# fuse-b-2.net
KiCad netlist of a schematic drawn in EAGLE
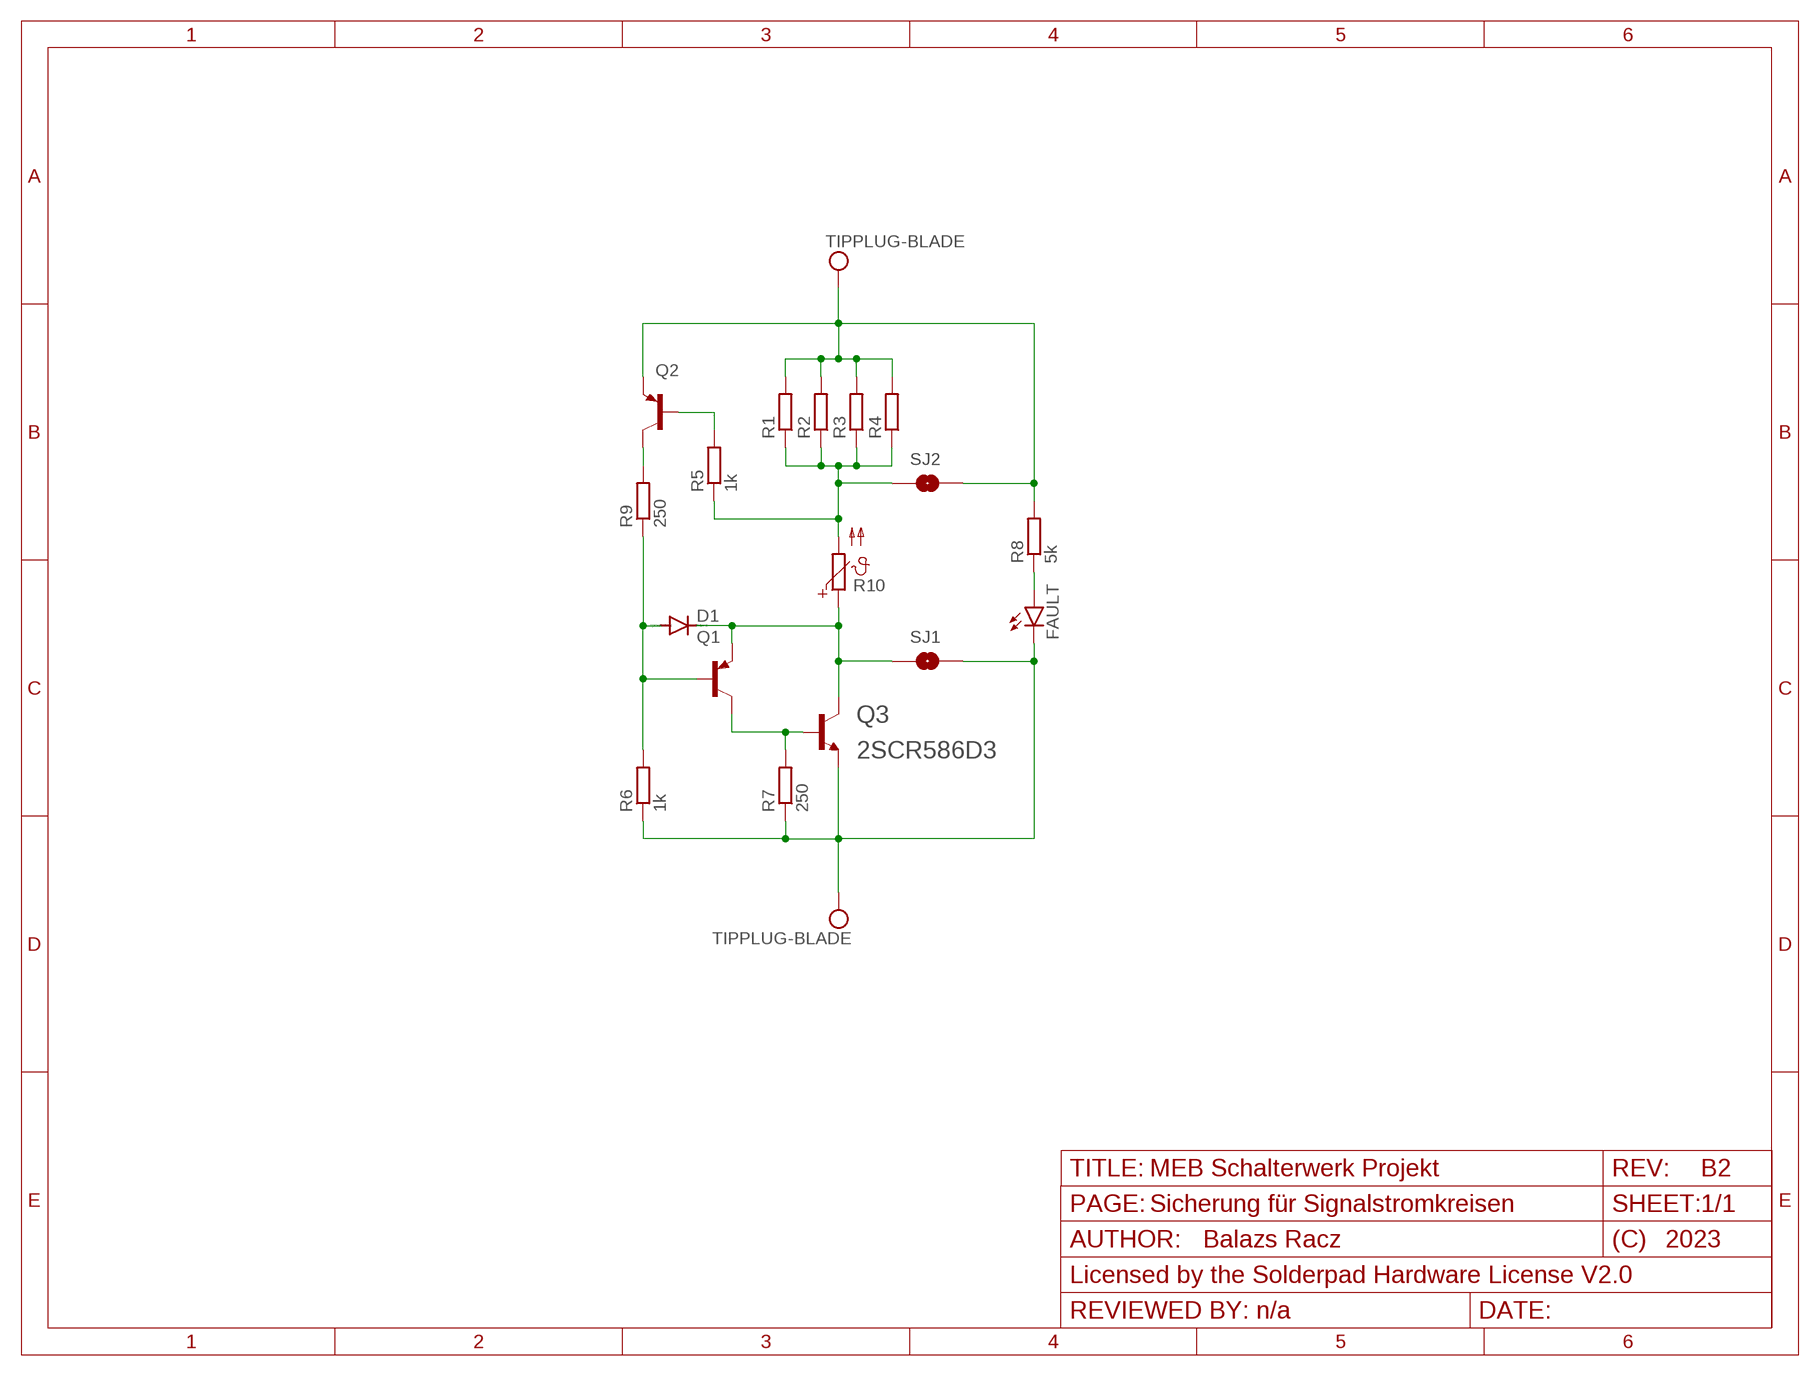
[diagram p0: schematic, sheet 1]

(export (version "E")
  (design (tool "Eeschema 10.0.6"))
  (components
    (comp (ref "D1")
      (value "DIODE-MINIMELF")
      (footprint "eagle-import:MINIMELF")
      (libsource (lib "eagle-import") (part "DIODE-MINIMELF"))
    )
    (comp (ref "FAULT")
      (value "LEDCHIPLED_0603")
      (footprint "eagle-import:CHIPLED_0603")
      (libsource (lib "eagle-import") (part "LEDCHIPLED_0603"))
    )
    (comp (ref "Q1")
      (value "BCX71SMD")
      (footprint "eagle-import:SOT23")
      (libsource (lib "eagle-import") (part "BCX71SMD"))
    )
    (comp (ref "Q2")
      (value "BCX71SMD")
      (footprint "eagle-import:SOT23")
      (libsource (lib "eagle-import") (part "BCX71SMD"))
    )
    (comp (ref "Q3")
      (value "2SCR586D3")
      (footprint "eagle-import:D-PAK_TO252AA")
      (libsource (lib "eagle-import") (part "2SCR586D3TL1"))
    )
    (comp (ref "R1")
      (value "R-EU_R2512")
      (footprint "eagle-import:R2512")
      (libsource (lib "eagle-import") (part "R-EU_R2512"))
    )
    (comp (ref "R2")
      (value "R-EU_R2512")
      (footprint "eagle-import:R2512")
      (libsource (lib "eagle-import") (part "R-EU_R2512"))
    )
    (comp (ref "R3")
      (value "R-EU_R2512")
      (footprint "eagle-import:R2512")
      (libsource (lib "eagle-import") (part "R-EU_R2512"))
    )
    (comp (ref "R4")
      (value "R-EU_R2512")
      (footprint "eagle-import:R2512")
      (libsource (lib "eagle-import") (part "R-EU_R2512"))
    )
    (comp (ref "R5")
      (value "1k")
      (footprint "eagle-import:R0805")
      (libsource (lib "eagle-import") (part "R-EU_R0805"))
    )
    (comp (ref "R6")
      (value "1k")
      (footprint "eagle-import:R0805")
      (libsource (lib "eagle-import") (part "R-EU_R0805"))
    )
    (comp (ref "R7")
      (value "250")
      (footprint "eagle-import:R0805")
      (libsource (lib "eagle-import") (part "R-EU_R0805"))
    )
    (comp (ref "R8")
      (value "5k")
      (footprint "eagle-import:R0805")
      (libsource (lib "eagle-import") (part "R-EU_R0805"))
    )
    (comp (ref "R9")
      (value "250")
      (footprint "eagle-import:R0805")
      (libsource (lib "eagle-import") (part "R-EU_R0805"))
    )
    (comp (ref "R10")
      (value "PTC_1812")
      (footprint "eagle-import:PTC1812")
      (libsource (lib "eagle-import") (part "PTC_1812"))
    )
    (comp (ref "SJ1")
      (value "SJRND2")
      (footprint "eagle-import:SJ_RND2")
      (libsource (lib "eagle-import") (part "SJRND2"))
    )
    (comp (ref "SJ2")
      (value "SJRND2")
      (footprint "eagle-import:SJ_RND2")
      (libsource (lib "eagle-import") (part "SJRND2"))
    )
    (comp (ref "U$1")
      (value "TIPPLUG-BLADE")
      (footprint "eagle-import:BLADEPLUG-9.5X1.25")
      (libsource (lib "eagle-import") (part "TIPPLUG-BLADE"))
    )
    (comp (ref "U$2")
      (value "TIPPLUG-BLADE")
      (footprint "eagle-import:BLADEPLUG-9.5X1.25")
      (libsource (lib "eagle-import") (part "TIPPLUG-BLADE"))
    )
  )
  (nets
    (net (code "1") (name "Net-(FAULT-PadA)") (class "Default")
      (node (ref "FAULT") (pin "A") (pinfunction "A_A") (pintype "passive"))
      (node (ref "R8") (pin "1") (pinfunction "1_1") (pintype "passive"))
    )
    (net (code "2") (name "Net-(Q1-B)") (class "Default")
      (node (ref "D1") (pin "A") (pinfunction "A_A") (pintype "passive"))
      (node (ref "Q1") (pin "1") (pinfunction "B_1") (pintype "passive"))
      (node (ref "R6") (pin "2") (pinfunction "2_2") (pintype "passive"))
      (node (ref "R9") (pin "1") (pinfunction "1_1") (pintype "passive"))
    )
    (net (code "3") (name "Net-(Q1-C)") (class "Default")
      (node (ref "Q1") (pin "3") (pinfunction "C_3") (pintype "passive"))
      (node (ref "Q3") (pin "1") (pinfunction "B_1") (pintype "passive"))
      (node (ref "R7") (pin "2") (pinfunction "2_2") (pintype "passive"))
    )
    (net (code "4") (name "Net-(Q1-E)") (class "Default")
      (node (ref "D1") (pin "C") (pinfunction "C_C") (pintype "passive"))
      (node (ref "Q1") (pin "2") (pinfunction "E_2") (pintype "passive"))
      (node (ref "Q3") (pin "4") (pinfunction "C_4") (pintype "passive"))
      (node (ref "R10") (pin "1") (pinfunction "1_1") (pintype "passive"))
      (node (ref "SJ1") (pin "P$1") (pinfunction "1_P$1") (pintype "passive"))
    )
    (net (code "5") (name "Net-(Q2-B)") (class "Default")
      (node (ref "Q2") (pin "1") (pinfunction "B_1") (pintype "passive"))
      (node (ref "R5") (pin "2") (pinfunction "2_2") (pintype "passive"))
    )
    (net (code "6") (name "Net-(Q2-C)") (class "Default")
      (node (ref "Q2") (pin "3") (pinfunction "C_3") (pintype "passive"))
      (node (ref "R9") (pin "2") (pinfunction "2_2") (pintype "passive"))
    )
    (net (code "7") (name "Net-(Q2-E)") (class "Default")
      (node (ref "Q2") (pin "2") (pinfunction "E_2") (pintype "passive"))
      (node (ref "R1") (pin "2") (pinfunction "2_2") (pintype "passive"))
      (node (ref "R2") (pin "2") (pinfunction "2_2") (pintype "passive"))
      (node (ref "R3") (pin "2") (pinfunction "2_2") (pintype "passive"))
      (node (ref "R4") (pin "2") (pinfunction "2_2") (pintype "passive"))
      (node (ref "R8") (pin "2") (pinfunction "2_2") (pintype "passive"))
      (node (ref "SJ2") (pin "P$2") (pinfunction "2_P$2") (pintype "passive"))
      (node (ref "U$1") (pin "PB") (pinfunction "$1_PB") (pintype "passive"))
      (node (ref "U$1") (pin "PT") (pinfunction "$1_PT") (pintype "passive"))
    )
    (net (code "8") (name "Net-(Q3-E)") (class "Default")
      (node (ref "FAULT") (pin "C") (pinfunction "C_C") (pintype "passive"))
      (node (ref "Q3") (pin "3") (pinfunction "E_3") (pintype "passive"))
      (node (ref "R6") (pin "1") (pinfunction "1_1") (pintype "passive"))
      (node (ref "R7") (pin "1") (pinfunction "1_1") (pintype "passive"))
      (node (ref "SJ1") (pin "P$2") (pinfunction "2_P$2") (pintype "passive"))
      (node (ref "U$2") (pin "PB") (pinfunction "$1_PB") (pintype "passive"))
      (node (ref "U$2") (pin "PT") (pinfunction "$1_PT") (pintype "passive"))
    )
    (net (code "9") (name "Net-(SJ2-1)") (class "Default")
      (node (ref "R1") (pin "1") (pinfunction "1_1") (pintype "passive"))
      (node (ref "R10") (pin "2") (pinfunction "2_2") (pintype "passive"))
      (node (ref "R2") (pin "1") (pinfunction "1_1") (pintype "passive"))
      (node (ref "R3") (pin "1") (pinfunction "1_1") (pintype "passive"))
      (node (ref "R4") (pin "1") (pinfunction "1_1") (pintype "passive"))
      (node (ref "R5") (pin "1") (pinfunction "1_1") (pintype "passive"))
      (node (ref "SJ2") (pin "P$1") (pinfunction "1_P$1") (pintype "passive"))
    )
  )
)
